# Mini_Arcade.net
KiCad netlist of a schematic drawn in EAGLE
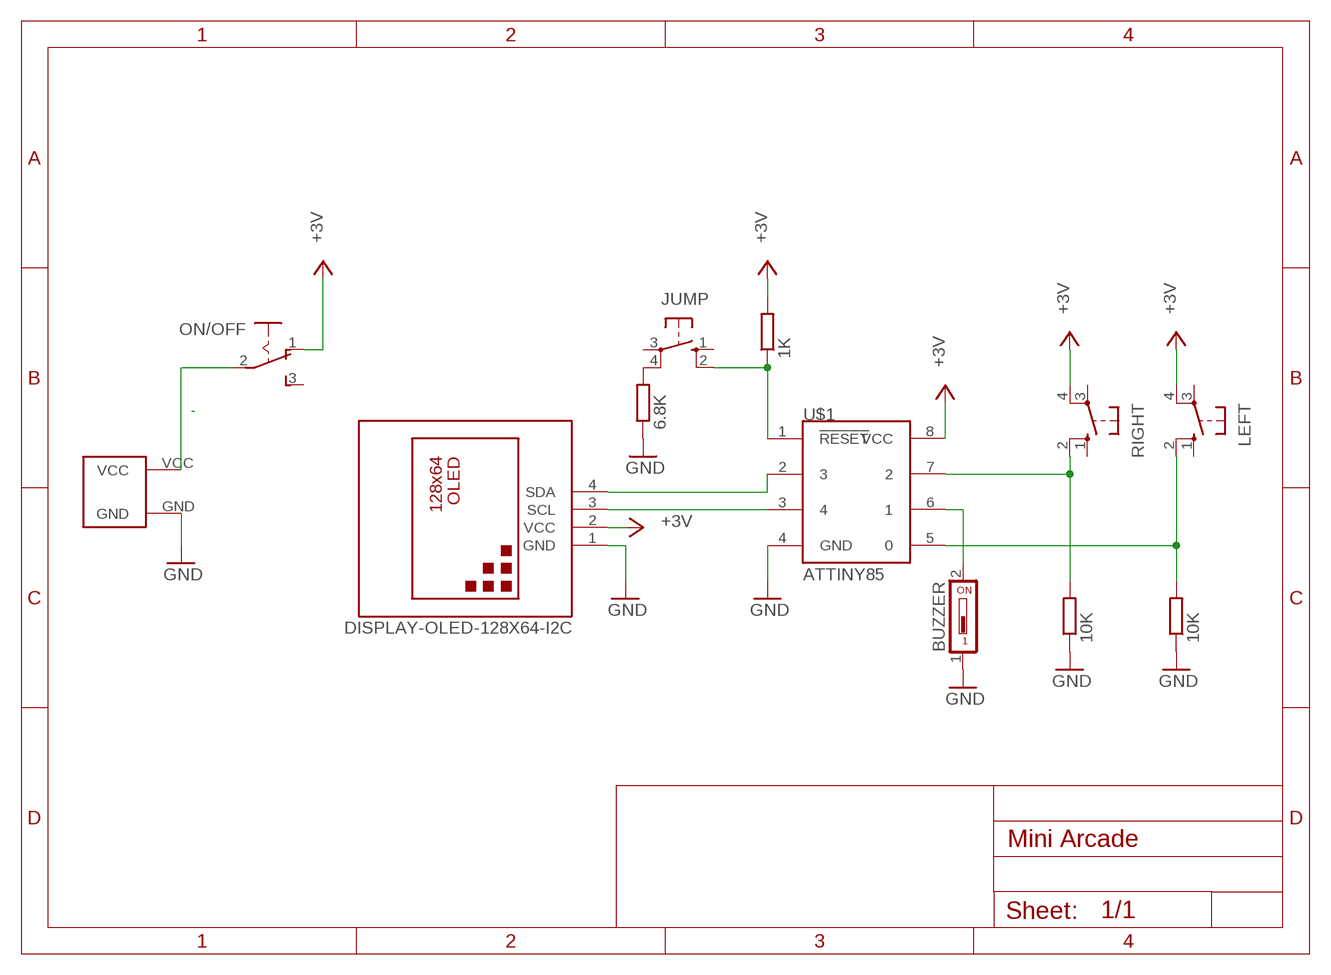
[diagram p0: schematic, sheet 1]

(export (version "E")
  (design (tool "Eeschema 10.0.6"))
  (components
    (comp (ref "BUZZER")
      (value "DS01")
      (footprint "eagle-import:DS-01")
      (libsource (lib "eagle-import") (part "DS01"))
    )
    (comp (ref "JUMP")
      (value "10-XX")
      (footprint "eagle-import:B3F-10XX")
      (fields (field (name "MPN") "B3F-1000"))
      (libsource (lib "eagle-import") (part "10-XX"))
    )
    (comp (ref "LEFT")
      (value "10-XX")
      (footprint "eagle-import:B3F-10XX")
      (fields (field (name "MPN") "B3F-1000"))
      (libsource (lib "eagle-import") (part "10-XX"))
    )
    (comp (ref "ON/OFF")
      (value "M251")
      (footprint "eagle-import:M251")
      (libsource (lib "eagle-import") (part "M251"))
    )
    (comp (ref "R1")
      (value "10K")
      (footprint "eagle-import:0207_10")
      (libsource (lib "eagle-import") (part "R-EU_0207/10"))
    )
    (comp (ref "R2")
      (value "10K")
      (footprint "eagle-import:0207_10")
      (libsource (lib "eagle-import") (part "R-EU_0207/10"))
    )
    (comp (ref "R3")
      (value "1K")
      (footprint "eagle-import:0207_10")
      (libsource (lib "eagle-import") (part "R-EU_0207/10"))
    )
    (comp (ref "R4")
      (value "6.8K")
      (footprint "eagle-import:0207_10")
      (libsource (lib "eagle-import") (part "R-EU_0207/10"))
    )
    (comp (ref "RIGHT")
      (value "10-XX")
      (footprint "eagle-import:B3F-10XX")
      (fields (field (name "MPN") "B3F-1000"))
      (libsource (lib "eagle-import") (part "10-XX"))
    )
    (comp (ref "U$1")
      (value "ATTINY85")
      (footprint "eagle-import:8P3")
      (libsource (lib "eagle-import") (part "ATTINY85"))
    )
    (comp (ref "U$2")
      (value "DISPLAY-OLED-128X64-I2C")
      (footprint "eagle-import:DISPLAY-OLED-128X64-I2C")
      (libsource (lib "eagle-import") (part "DISPLAY-OLED-128X64-I2C"))
    )
    (comp (ref "U$5")
      (value "CR2032")
      (footprint "eagle-import:CR2032-20MM")
      (libsource (lib "eagle-import") (part "CR2032"))
    )
  )
  (nets
    (net (code "1") (name "+3V") (class "Default")
      (node (ref "LEFT") (pin "4") (pinfunction "P1_4") (pintype "passive"))
      (node (ref "ON/OFF") (pin "1") (pinfunction "O_1") (pintype "passive"))
      (node (ref "R3") (pin "2") (pinfunction "2_2") (pintype "passive"))
      (node (ref "RIGHT") (pin "4") (pinfunction "P1_4") (pintype "passive"))
      (node (ref "U$1") (pin "8") (pinfunction "VCC_8") (pintype "power_in"))
      (node (ref "U$2") (pin "2") (pinfunction "VCC_2") (pintype "power_in"))
    )
    (net (code "2") (name "GND") (class "Default")
      (node (ref "BUZZER") (pin "1") (pinfunction "1_1") (pintype "passive"))
      (node (ref "R1") (pin "1") (pinfunction "1_1") (pintype "passive"))
      (node (ref "R2") (pin "1") (pinfunction "1_1") (pintype "passive"))
      (node (ref "R4") (pin "1") (pinfunction "1_1") (pintype "passive"))
      (node (ref "U$1") (pin "4") (pinfunction "GND_4") (pintype "power_in"))
      (node (ref "U$2") (pin "1") (pinfunction "GND_1") (pintype "power_in"))
      (node (ref "U$5") (pin "GND") (pinfunction "GND_GND") (pintype "bidirectional"))
    )
    (net (code "3") (name "Net-(JUMP-P1)") (class "Default")
      (node (ref "JUMP") (pin "4") (pinfunction "P1_4") (pintype "passive"))
      (node (ref "R4") (pin "2") (pinfunction "2_2") (pintype "passive"))
    )
    (net (code "4") (name "Net-(JUMP-S1)") (class "Default")
      (node (ref "JUMP") (pin "2") (pinfunction "S1_2") (pintype "passive"))
      (node (ref "R3") (pin "1") (pinfunction "1_1") (pintype "passive"))
      (node (ref "U$1") (pin "1") (pinfunction "~{RESET}_1") (pintype "bidirectional"))
    )
    (net (code "5") (name "Net-(LEFT-S1)") (class "Default")
      (node (ref "LEFT") (pin "2") (pinfunction "S1_2") (pintype "passive"))
      (node (ref "R2") (pin "2") (pinfunction "2_2") (pintype "passive"))
      (node (ref "U$1") (pin "5") (pinfunction "0_5") (pintype "bidirectional"))
    )
    (net (code "6") (name "Net-(ON/OFF-P)") (class "Default")
      (node (ref "ON/OFF") (pin "2") (pinfunction "P_2") (pintype "passive"))
      (node (ref "U$5") (pin "VCC") (pinfunction "VCC_VCC") (pintype "bidirectional"))
    )
    (net (code "7") (name "Net-(RIGHT-S1)") (class "Default")
      (node (ref "R1") (pin "2") (pinfunction "2_2") (pintype "passive"))
      (node (ref "RIGHT") (pin "2") (pinfunction "S1_2") (pintype "passive"))
      (node (ref "U$1") (pin "7") (pinfunction "2_7") (pintype "bidirectional"))
    )
    (net (code "8") (name "Net-(U$1-1)") (class "Default")
      (node (ref "BUZZER") (pin "2") (pinfunction "2_2") (pintype "passive"))
      (node (ref "U$1") (pin "6") (pinfunction "1_6") (pintype "bidirectional"))
    )
    (net (code "9") (name "Net-(U$1-3)") (class "Default")
      (node (ref "U$1") (pin "2") (pinfunction "3_2") (pintype "bidirectional"))
      (node (ref "U$2") (pin "4") (pinfunction "SDA_4") (pintype "bidirectional"))
    )
    (net (code "10") (name "Net-(U$1-4)") (class "Default")
      (node (ref "U$1") (pin "3") (pinfunction "4_3") (pintype "bidirectional"))
      (node (ref "U$2") (pin "3") (pinfunction "SCL_3") (pintype "bidirectional"))
    )
    (net (code "11") (name "unconnected-(JUMP-P-Pad3)") (class "Default")
      (node (ref "JUMP") (pin "3") (pinfunction "P_3") (pintype "passive"))
    )
    (net (code "12") (name "unconnected-(JUMP-S-Pad1)") (class "Default")
      (node (ref "JUMP") (pin "1") (pinfunction "S_1") (pintype "passive"))
    )
    (net (code "13") (name "unconnected-(LEFT-P-Pad3)") (class "Default")
      (node (ref "LEFT") (pin "3") (pinfunction "P_3") (pintype "passive"))
    )
    (net (code "14") (name "unconnected-(LEFT-S-Pad1)") (class "Default")
      (node (ref "LEFT") (pin "1") (pinfunction "S_1") (pintype "passive"))
    )
    (net (code "15") (name "unconnected-(ON/OFF-S-Pad3)") (class "Default")
      (node (ref "ON/OFF") (pin "3") (pinfunction "S_3") (pintype "passive"))
    )
    (net (code "16") (name "unconnected-(RIGHT-P-Pad3)") (class "Default")
      (node (ref "RIGHT") (pin "3") (pinfunction "P_3") (pintype "passive"))
    )
    (net (code "17") (name "unconnected-(RIGHT-S-Pad1)") (class "Default")
      (node (ref "RIGHT") (pin "1") (pinfunction "S_1") (pintype "passive"))
    )
  )
)
